# ConectoresAdicionales.net
KiCad netlist of a schematic drawn in Altium Designer
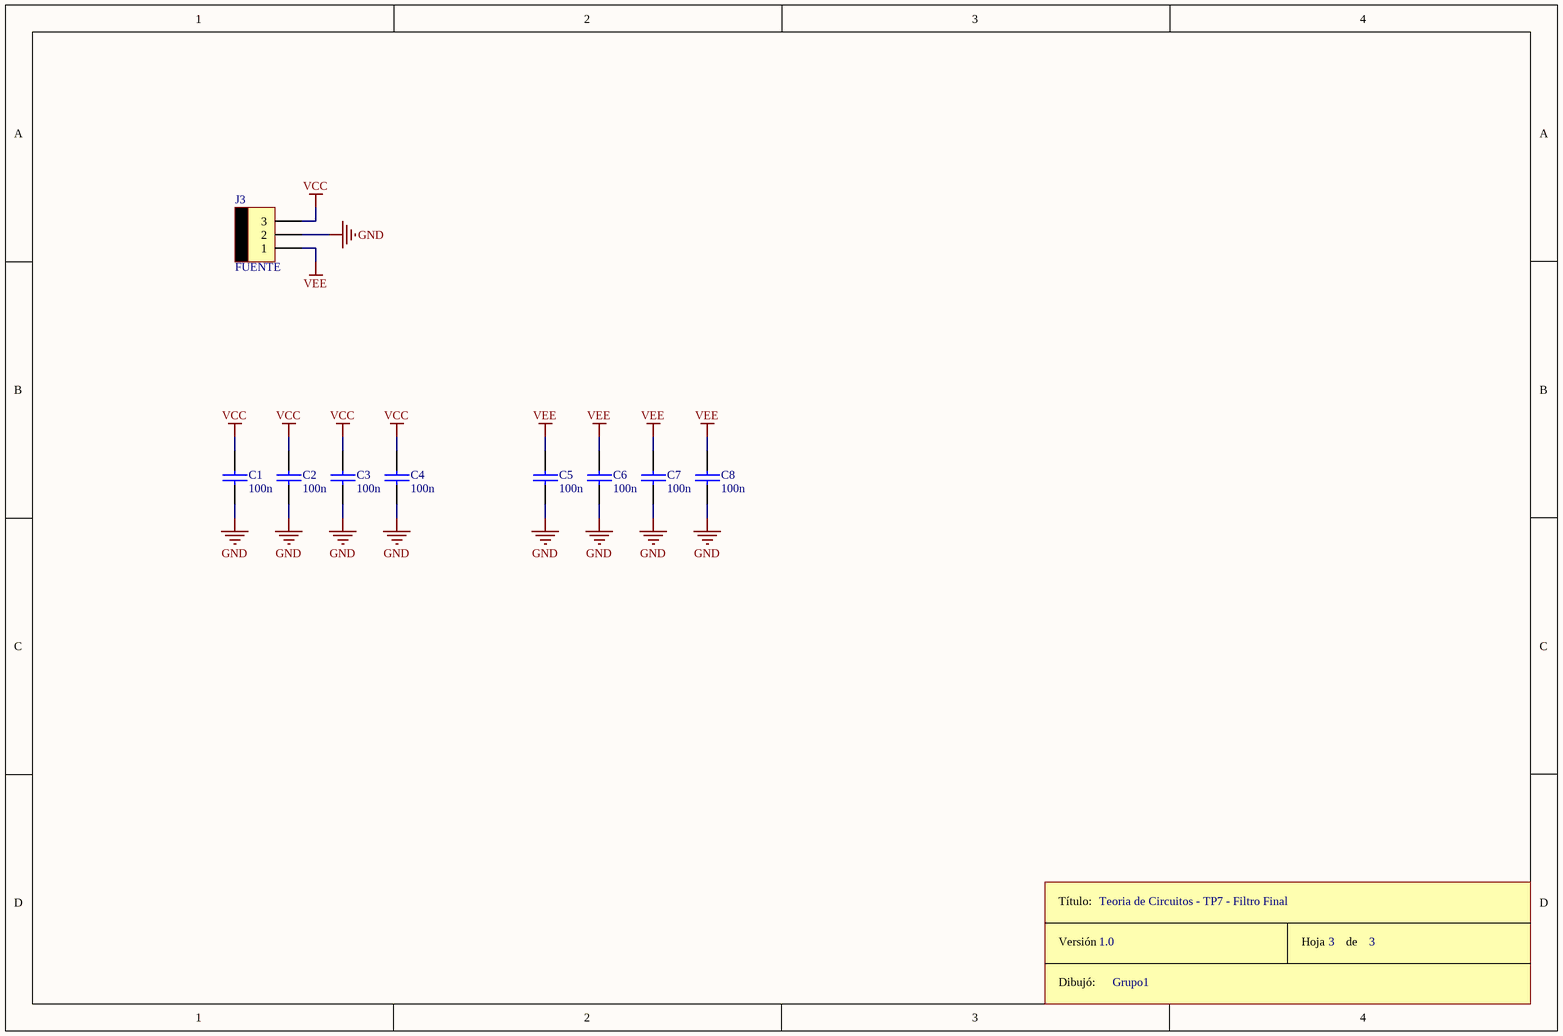
[diagram p0: ConectoresAdicionales.SchDoc]

(export (version "E")
  (design (tool "Eeschema 10.0.6"))
  (components
    (comp (ref "C1") (value "100n") (footprint "CAP200") (libsource (lib "LIB PIO IX") (part "CAP")))
    (comp (ref "C2") (value "100n") (footprint "CAP200") (libsource (lib "LIB PIO IX") (part "CAP")))
    (comp (ref "C3") (value "100n") (footprint "CAP200") (libsource (lib "LIB PIO IX") (part "CAP")))
    (comp (ref "C4") (value "100n") (footprint "CAP200") (libsource (lib "LIB PIO IX") (part "CAP")))
    (comp (ref "C5") (value "100n") (footprint "CAP200") (libsource (lib "LIB PIO IX") (part "CAP")))
    (comp (ref "C6") (value "100n") (footprint "CAP200") (libsource (lib "LIB PIO IX") (part "CAP")))
    (comp (ref "C7") (value "100n") (footprint "CAP200") (libsource (lib "LIB PIO IX") (part "CAP")))
    (comp (ref "C8") (value "100n") (footprint "CAP200") (libsource (lib "LIB PIO IX") (part "CAP")))
    (comp (ref "J3") (value "FUENTE") (footprint "MOLEX3") (libsource (lib "LIB PIO IX") (part "MOLEX3")))
    (comp (ref "ROT3") (value "Rótulo") (libsource (lib "LIB PIO IX") (part "Rótulo")))
  )
  (nets
    (net (code "1") (name "GND") (class "Default")
      (node (ref "C1") (pin "2") (pinfunction "2_2") (pintype "passive"))
      (node (ref "C2") (pin "2") (pinfunction "2_2") (pintype "passive"))
      (node (ref "C3") (pin "2") (pinfunction "2_2") (pintype "passive"))
      (node (ref "C4") (pin "2") (pinfunction "2_2") (pintype "passive"))
      (node (ref "C5") (pin "2") (pinfunction "2_2") (pintype "passive"))
      (node (ref "C6") (pin "2") (pinfunction "2_2") (pintype "passive"))
      (node (ref "C7") (pin "2") (pinfunction "2_2") (pintype "passive"))
      (node (ref "C8") (pin "2") (pinfunction "2_2") (pintype "passive"))
      (node (ref "J3") (pin "2") (pinfunction "2_2") (pintype "passive"))
    )
    (net (code "2") (name "VCC") (class "Default")
      (node (ref "C1") (pin "1") (pinfunction "1_1") (pintype "passive"))
      (node (ref "C2") (pin "1") (pinfunction "1_1") (pintype "passive"))
      (node (ref "C3") (pin "1") (pinfunction "1_1") (pintype "passive"))
      (node (ref "C4") (pin "1") (pinfunction "1_1") (pintype "passive"))
      (node (ref "J3") (pin "3") (pinfunction "3_3") (pintype "passive"))
    )
    (net (code "3") (name "VEE") (class "Default")
      (node (ref "C5") (pin "1") (pinfunction "1_1") (pintype "passive"))
      (node (ref "C6") (pin "1") (pinfunction "1_1") (pintype "passive"))
      (node (ref "C7") (pin "1") (pinfunction "1_1") (pintype "passive"))
      (node (ref "C8") (pin "1") (pinfunction "1_1") (pintype "passive"))
      (node (ref "J3") (pin "1") (pinfunction "1_1") (pintype "passive"))
    )
  )
)
